# Sch1.net
KiCad netlist of a schematic drawn in Altium Designer
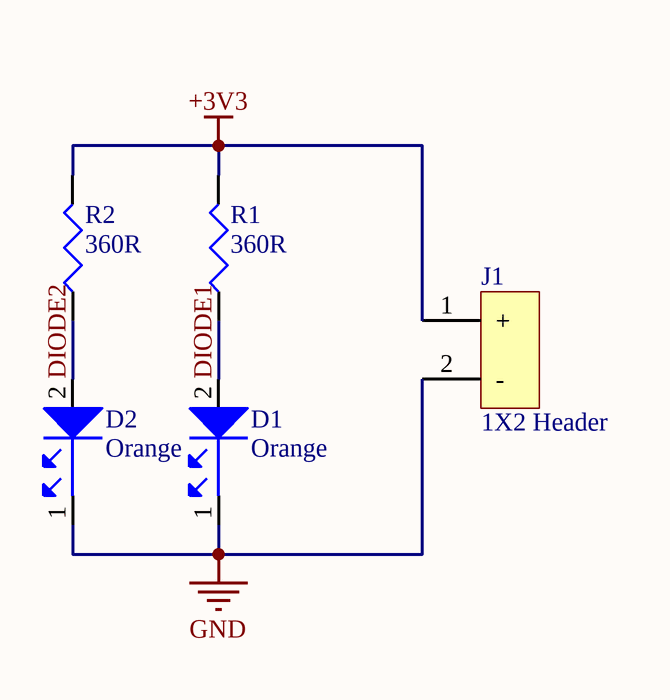
[diagram p0: Sch1.SchDoc]

(export (version "E")
  (design (tool "Eeschema 10.0.6"))
  (components
    (comp (ref "D1")
      (value "Orange")
      (footprint "LED0603 O")
      (description "Orange 620nm LED Indication - Discrete 1.95V 0603 (1608 Metric)")
      (fields
        (field (name "MANUFACTURER") "Panasonic SSG")
        (field (name "MANUFACTURER PART NUMBER") "LNJ8W0C83RA")
      )
      (libsource (lib "new_Schlib1") (part "LNJ8W0C83RA"))
    )
    (comp (ref "D2")
      (value "Orange")
      (footprint "LED0603 O")
      (description "Orange 620nm LED Indication - Discrete 1.95V 0603 (1608 Metric)")
      (fields
        (field (name "MANUFACTURER") "Panasonic SSG")
        (field (name "MANUFACTURER PART NUMBER") "LNJ8W0C83RA")
      )
      (libsource (lib "new_Schlib1") (part "LNJ8W0C83RA"))
    )
    (comp (ref "J1")
      (value "1X2 Header")
      (footprint "New_PcbLib1:Header 1x2")
      (description "CONN HEADER 2POS .100 VERT TIN")
      (fields (field (name "MANUFACTURER") "Molex") (field (name "MANUFACTURER PART NUMBER") "22-27-2021"))
      (libsource (lib "new_Schlib1") (part "22-27-2021"))
    )
    (comp (ref "R1")
      (value "360R")
      (footprint "R0805")
      (description "RES SMD 360 OHM 1% 1/8W 0805")
      (fields
        (field (name "MANUFACTURER") "Vishay")
        (field (name "MANUFACTURER PART NUMBER") "CRCW0805360RFKEA")
      )
      (libsource (lib "new_Schlib1") (part "CRCW0805360RFKEA"))
    )
    (comp (ref "R2")
      (value "360R")
      (footprint "R0805")
      (description "RES SMD 360 OHM 1% 1/8W 0805")
      (fields
        (field (name "MANUFACTURER") "Vishay")
        (field (name "MANUFACTURER PART NUMBER") "CRCW0805360RFKEA")
      )
      (libsource (lib "new_Schlib1") (part "CRCW0805360RFKEA"))
    )
  )
  (nets
    (net (code "1") (name "+3V3") (class "Default")
      (node (ref "J1") (pin "1") (pinfunction "+_1") (pintype "passive"))
      (node (ref "R1") (pin "2") (pinfunction "2_2") (pintype "passive"))
      (node (ref "R2") (pin "2") (pinfunction "2_2") (pintype "passive"))
    )
    (net (code "2") (name "/DIODE1") (class "Default")
      (node (ref "D1") (pin "2") (pinfunction "2_2") (pintype "passive"))
      (node (ref "R1") (pin "1") (pinfunction "1_1") (pintype "passive"))
    )
    (net (code "3") (name "/DIODE2") (class "Default")
      (node (ref "D2") (pin "2") (pinfunction "2_2") (pintype "passive"))
      (node (ref "R2") (pin "1") (pinfunction "1_1") (pintype "passive"))
    )
    (net (code "4") (name "GND") (class "Default")
      (node (ref "D1") (pin "1") (pinfunction "1_1") (pintype "passive"))
      (node (ref "D2") (pin "1") (pinfunction "1_1") (pintype "passive"))
      (node (ref "J1") (pin "2") (pinfunction "-_2") (pintype "passive"))
    )
  )
)
